# DRV8886_Power_Breakout.net
KiCad netlist of a schematic drawn in Altium Designer
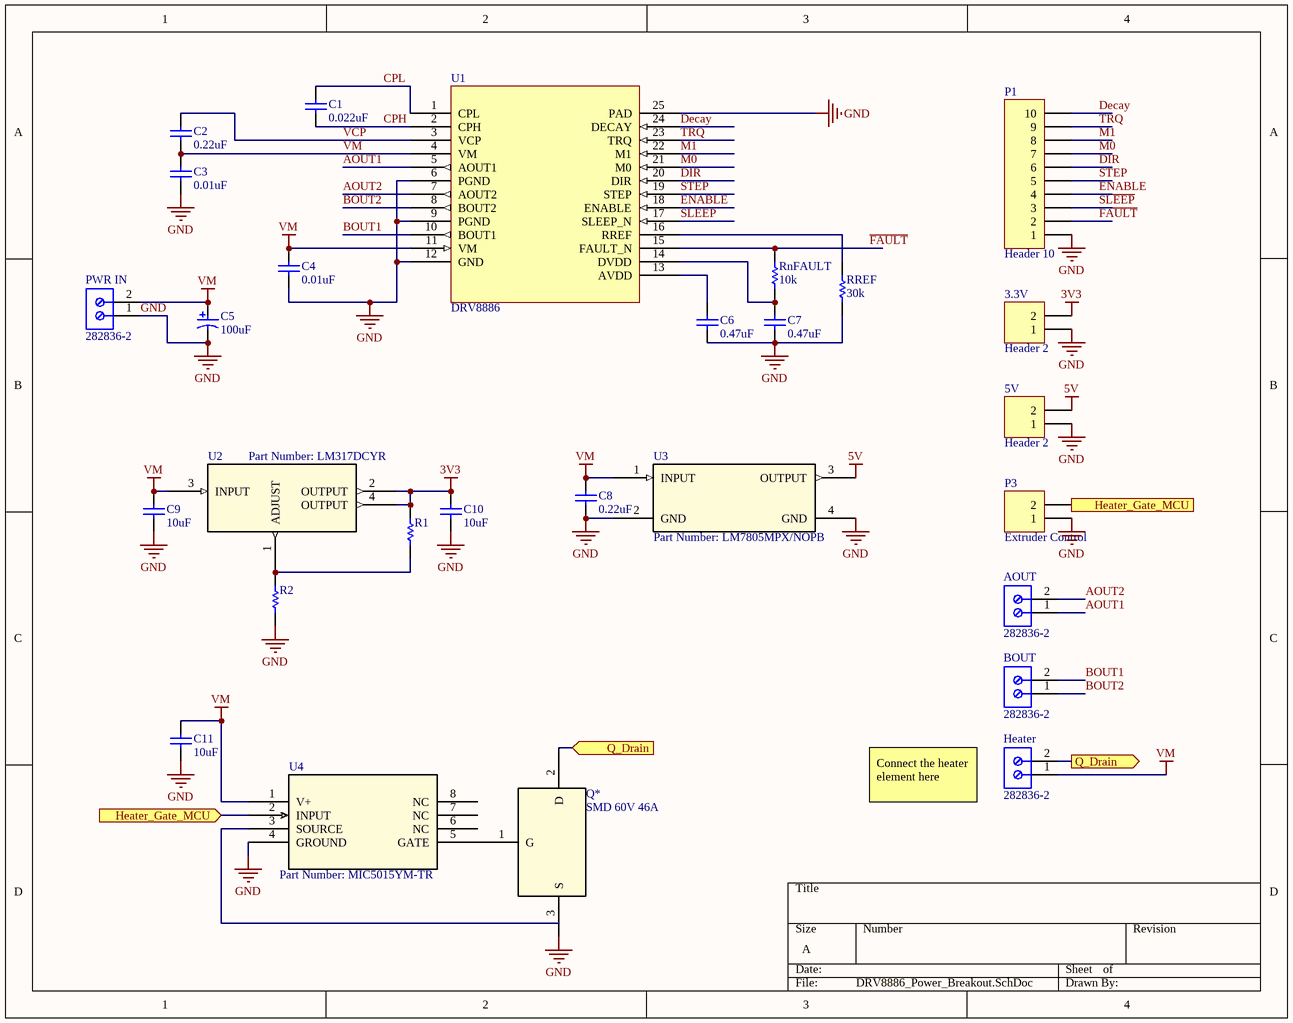
[diagram p0: DRV8886_Power_Breakout.SchDoc]

(export (version "E")
  (design (tool "Eeschema 10.0.6"))
  (components
    (comp (ref "3.3V")
      (value "Header 2")
      (footprint "HDR1X2")
      (description "Header, 2-Pin")
      (fields (field (name "PUBLISHER") "Altium Limited"))
      (libsource (lib "Miscellaneous Connectors") (part "Header 2"))
    )
    (comp (ref "5V")
      (value "Header 2")
      (footprint "HDR1X2")
      (description "Header, 2-Pin")
      (fields (field (name "PUBLISHER") "Altium Limited"))
      (libsource (lib "Miscellaneous Connectors") (part "Header 2"))
    )
    (comp (ref "AOUT")
      (value "282836-2")
      (footprint "TECO-282836-2_V")
      (description "Female Header, Pitch 5 mm, 1 x 2 Position, Height 10 mm, Tail Length 3.5 mm, Rohs, Bulk")
      (fields (field (name "VOLTAGE") "300V") (field (name "MANUFACTURER") "TE Connectivity"))
      (libsource (lib "IFFF_DRV8886_Power_Breakout") (part "CMP-1684-00017-1"))
    )
    (comp (ref "BOUT")
      (value "282836-2")
      (footprint "TECO-282836-2_V")
      (description "Female Header, Pitch 5 mm, 1 x 2 Position, Height 10 mm, Tail Length 3.5 mm, Rohs, Bulk")
      (fields (field (name "VOLTAGE") "300V") (field (name "MANUFACTURER") "TE Connectivity"))
      (libsource (lib "IFFF_DRV8886_Power_Breakout") (part "CMP-1684-00017-1"))
    )
    (comp (ref "C1")
      (value "0.022uF")
      (footprint "CAPC2013X94X50ML20T25")
      (fields
        (field (name "MANUFACTURER") "AVX Interconnect / Elco")
        (field (name "PART NUMBER") "08055C223JAT2A")
      )
      (libsource (lib "Altium Content Vault") (part "CAP"))
    )
    (comp (ref "C2")
      (value "0.22uF")
      (footprint "CAPC2013X145X50NL20T25")
      (description "0805")
      (fields (field (name "PART NUMBER") "C0805C224K5RAC7800") (field (name "MANUFACTURER") "Kemet"))
      (libsource (lib "Altium Content Vault") (part "CAP"))
    )
    (comp (ref "C3")
      (value "0.01uF")
      (footprint "CAPC2013X88X50ML20T25")
      (description "0805")
      (fields (field (name "MANUFACTURER") "Kemet") (field (name "PART NUMBER") "C0805C103J5RACTU"))
      (libsource (lib "Altium Content Vault") (part "CAP"))
    )
    (comp (ref "C4")
      (value "0.01uF")
      (footprint "CAPC2013X88X50ML20T25")
      (description "0805")
      (fields (field (name "MANUFACTURER") "Kemet") (field (name "PART NUMBER") "C0805C103J5RACTU"))
      (libsource (lib "Altium Content Vault") (part "CAP"))
    )
    (comp (ref "C5")
      (value "100uF")
      (footprint "PNSC-FK-V-F_V")
      (fields (field (name "MANUFACTURER") "Panasonic"))
      (libsource (lib "Altium Content Vault") (part "CAP-P-2"))
    )
    (comp (ref "C6")
      (value "0.47uF")
      (footprint "CAPC2013X110X50NL20T25")
      (description "0805")
      (fields (field (name "MANUFACTURER") "Kemet") (field (name "PART NUMBER") "C0805C474K5RACTU"))
      (libsource (lib "Altium Content Vault") (part "CAP"))
    )
    (comp (ref "C7")
      (value "0.47uF")
      (footprint "CAPC2013X110X50NL20T25")
      (description "0805")
      (fields (field (name "MANUFACTURER") "Kemet") (field (name "PART NUMBER") "C0805C474K5RACTU"))
      (libsource (lib "Altium Content Vault") (part "CAP"))
    )
    (comp (ref "C8")
      (value "0.22uF")
      (footprint "CAPC2013X145X50NL20T25")
      (description "0805")
      (fields (field (name "PART NUMBER") "C0805C224K5RAC7800") (field (name "MANUFACTURER") "Kemet"))
      (libsource (lib "Altium Content Vault") (part "CAP"))
    )
    (comp (ref "C9")
      (value "10uF")
      (footprint "CAPC2013X135X45ML10T25")
      (description "0805")
      (fields (field (name "PART NUMBER") "GRM21BR61E106KA73L") (field (name "MANUFACTURER") "Murata"))
      (libsource (lib "Altium Content Vault") (part "CAP"))
    )
    (comp (ref "C10")
      (value "10uF")
      (footprint "CAPC2013X135X45ML10T25")
      (description "0805")
      (fields (field (name "PART NUMBER") "GRM21BR61E106KA73L") (field (name "MANUFACTURER") "Murata"))
      (libsource (lib "Altium Content Vault") (part "CAP"))
    )
    (comp (ref "C11")
      (value "10uF")
      (footprint "CAPC2013X135X45ML10T25")
      (description "0805")
      (fields (field (name "PART NUMBER") "GRM21BR61E106KA73L") (field (name "MANUFACTURER") "Murata"))
      (libsource (lib "Altium Content Vault") (part "CAP"))
    )
    (comp (ref "Heater")
      (value "282836-2")
      (footprint "TECO-282836-2_V")
      (description "Female Header, Pitch 5 mm, 1 x 2 Position, Height 10 mm, Tail Length 3.5 mm, Rohs, Bulk")
      (fields (field (name "VOLTAGE") "300V") (field (name "MANUFACTURER") "TE Connectivity"))
      (libsource (lib "IFFF_DRV8886_Power_Breakout") (part "CMP-1684-00017-1"))
    )
    (comp (ref "P1")
      (value "Header 10")
      (footprint "HDR1X10")
      (description "Header, 10-Pin")
      (fields (field (name "PUBLISHER") "Altium Limited"))
      (libsource (lib "Miscellaneous Connectors") (part "Header 10"))
    )
    (comp (ref "P3")
      (value "Extruder Control")
      (footprint "HDR1X2")
      (description "Header, 2-Pin")
      (fields (field (name "PUBLISHER") "Altium Limited"))
      (libsource (lib "Miscellaneous Connectors") (part "Header 2"))
    )
    (comp (ref "PWR IN")
      (value "282836-2")
      (footprint "TECO-282836-2_V")
      (description "Female Header, Pitch 5 mm, 1 x 2 Position, Height 10 mm, Tail Length 3.5 mm, Rohs, Bulk")
      (fields (field (name "VOLTAGE") "300V") (field (name "MANUFACTURER") "TE Connectivity"))
      (libsource (lib "IFFF_DRV8886_Power_Breakout") (part "CMP-1684-00017-1"))
    )
    (comp (ref "Q*")
      (value "SMD 60V 46A")
      (footprint "SC_TO-252AA")
      (description "N-Channel 60V 46A (Tc) 71W (Tc) Surface Mount DPAK")
      (libsource (lib "IFFF_DRV8886_Power_Breakout") (part "NTD5865NLT4G"))
    )
    (comp (ref "R1")
      (value "~")
      (footprint "RESC2013X60X40LL20T25_A")
      (fields (field (name "TOLERANCE") "0.1%") (field (name "MANUFACTURER") "Panasonic"))
      (libsource (lib "Altium Content Vault") (part "RES-2"))
    )
    (comp (ref "R2")
      (value "~")
      (footprint "RESC2013X60X40LL20T25_A")
      (fields (field (name "TOLERANCE") "0.1%") (field (name "MANUFACTURER") "Panasonic"))
      (libsource (lib "Altium Content Vault") (part "RES-2"))
    )
    (comp (ref "RnFAULT")
      (value "10k")
      (footprint "RESC2013X60X40LL20T25_A")
      (fields (field (name "TOLERANCE") "0.1%") (field (name "MANUFACTURER") "Panasonic"))
      (libsource (lib "Altium Content Vault") (part "RES-2"))
    )
    (comp (ref "RREF")
      (value "30k")
      (footprint "RESC2013X60X40LL20T25_A")
      (fields (field (name "TOLERANCE") "0.1%") (field (name "MANUFACTURER") "Panasonic"))
      (libsource (lib "Altium Content Vault") (part "RES-2"))
    )
    (comp (ref "U1")
      (value "DRV8886")
      (footprint "PWP0024B_N")
      (libsource (lib "IFFF_DRV8886_Power_Breakout") (part "DRV8886"))
    )
    (comp (ref "U2")
      (value "Part Number: LM317DCYR")
      (footprint "DCY4")
      (description "No Description Available")
      (fields
        (field (name "MANUFACTURER_PART_NUMBER") "LM317DCYR")
        (field (name "COPYRIGHT") "Copyright (C) 2018 Accelerated Designs. All rights reserved")
      )
      (libsource (lib "IFFF_DRV8886_Power_Breakout") (part "LM317DCYR"))
    )
    (comp (ref "U3")
      (value "Part Number: LM7805MPX/NOPB")
      (footprint "DCY4")
      (description "No Description Available")
      (fields
        (field (name "MANUFACTURER_PART_NUMBER") "LM7805MPX/NOPB")
        (field (name "COPYRIGHT") "Copyright (C) 2018 Accelerated Designs. All rights reserved")
      )
      (libsource (lib "IFFF_DRV8886_Power_Breakout") (part "LM7805MPX/NOPB"))
    )
    (comp (ref "U4")
      (value "Part Number: MIC5015YM-TR")
      (footprint "SOIC-8_M")
      (description "No Description Available")
      (fields
        (field (name "MANUFACTURER_PART_NUMBER") "MIC5015YM-TR")
        (field (name "COPYRIGHT") "Copyright (C) 2018 Accelerated Designs. All rights reserved")
      )
      (libsource (lib "IFFF_DRV8886_Power_Breakout") (part "MIC5015YM-TR"))
    )
  )
  (nets
    (net (code "1") (name "/AOUT1") (class "Default")
      (node (ref "AOUT") (pin "1") (pinfunction "1_1") (pintype "passive"))
      (node (ref "U1") (pin "5") (pinfunction "AOUT1_5") (pintype "output"))
    )
    (net (code "2") (name "/AOUT2") (class "Default")
      (node (ref "AOUT") (pin "2") (pinfunction "2_2") (pintype "passive"))
      (node (ref "U1") (pin "7") (pinfunction "AOUT2_7") (pintype "output"))
    )
    (net (code "3") (name "/BOUT1") (class "Default")
      (node (ref "BOUT") (pin "2") (pinfunction "2_2") (pintype "passive"))
      (node (ref "U1") (pin "10") (pinfunction "BOUT1_10") (pintype "output"))
    )
    (net (code "4") (name "/BOUT2") (class "Default")
      (node (ref "BOUT") (pin "1") (pinfunction "1_1") (pintype "passive"))
      (node (ref "U1") (pin "8") (pinfunction "BOUT2_8") (pintype "output"))
    )
    (net (code "5") (name "/CPH") (class "Default")
      (node (ref "C1") (pin "1") (pinfunction "1_1") (pintype "passive"))
      (node (ref "U1") (pin "2") (pinfunction "CPH_2") (pintype "passive"))
    )
    (net (code "6") (name "/CPL") (class "Default")
      (node (ref "C1") (pin "2") (pinfunction "2_2") (pintype "passive"))
      (node (ref "U1") (pin "1") (pinfunction "CPL_1") (pintype "passive"))
    )
    (net (code "7") (name "/DIR") (class "Default")
      (node (ref "P1") (pin "6") (pinfunction "6_6") (pintype "passive"))
      (node (ref "U1") (pin "20") (pinfunction "DIR_20") (pintype "input"))
    )
    (net (code "8") (name "/Decay") (class "Default")
      (node (ref "P1") (pin "10") (pinfunction "10_10") (pintype "passive"))
      (node (ref "U1") (pin "24") (pinfunction "DECAY_24") (pintype "input"))
    )
    (net (code "9") (name "/ENABLE") (class "Default")
      (node (ref "P1") (pin "4") (pinfunction "4_4") (pintype "passive"))
      (node (ref "U1") (pin "18") (pinfunction "ENABLE_18") (pintype "input"))
    )
    (net (code "10") (name "/FAULT") (class "Default")
      (node (ref "P1") (pin "2") (pinfunction "2_2") (pintype "passive"))
      (node (ref "RnFAULT") (pin "2") (pinfunction "2_2") (pintype "passive"))
      (node (ref "U1") (pin "15") (pinfunction "FAULT_N_15") (pintype "passive"))
    )
    (net (code "11") (name "/Heater_Gate_MCU") (class "Default")
      (node (ref "P3") (pin "2") (pinfunction "2_2") (pintype "passive"))
      (node (ref "U4") (pin "2") (pinfunction "INPUT_2") (pintype "input"))
    )
    (net (code "12") (name "/M0") (class "Default")
      (node (ref "P1") (pin "7") (pinfunction "7_7") (pintype "passive"))
      (node (ref "U1") (pin "21") (pinfunction "M0_21") (pintype "input"))
    )
    (net (code "13") (name "/M1") (class "Default")
      (node (ref "P1") (pin "8") (pinfunction "8_8") (pintype "passive"))
      (node (ref "U1") (pin "22") (pinfunction "M1_22") (pintype "input"))
    )
    (net (code "14") (name "/Q_Drain") (class "Default")
      (node (ref "Heater") (pin "2") (pinfunction "2_2") (pintype "passive"))
      (node (ref "Q*") (pin "2") (pinfunction "D_2") (pintype "passive"))
    )
    (net (code "15") (name "/SLEEP") (class "Default")
      (node (ref "P1") (pin "3") (pinfunction "3_3") (pintype "passive"))
      (node (ref "U1") (pin "17") (pinfunction "SLEEP_N_17") (pintype "input"))
    )
    (net (code "16") (name "/STEP") (class "Default")
      (node (ref "P1") (pin "5") (pinfunction "5_5") (pintype "passive"))
      (node (ref "U1") (pin "19") (pinfunction "STEP_19") (pintype "input"))
    )
    (net (code "17") (name "/TRQ") (class "Default")
      (node (ref "P1") (pin "9") (pinfunction "9_9") (pintype "passive"))
      (node (ref "U1") (pin "23") (pinfunction "TRQ_23") (pintype "input"))
    )
    (net (code "18") (name "/VCP") (class "Default")
      (node (ref "C2") (pin "2") (pinfunction "2_2") (pintype "passive"))
      (node (ref "U1") (pin "3") (pinfunction "VCP_3") (pintype "passive"))
    )
    (net (code "19") (name "3V3") (class "Default")
      (node (ref "3.3V") (pin "2") (pinfunction "2_2") (pintype "passive"))
      (node (ref "C10") (pin "1") (pinfunction "1_1") (pintype "passive"))
      (node (ref "R1") (pin "2") (pinfunction "2_2") (pintype "passive"))
      (node (ref "U2") (pin "2") (pinfunction "OUTPUT_2") (pintype "output"))
      (node (ref "U2") (pin "4") (pinfunction "OUTPUT_4") (pintype "output"))
    )
    (net (code "20") (name "5V") (class "Default")
      (node (ref "5V") (pin "2") (pinfunction "2_2") (pintype "passive"))
      (node (ref "U3") (pin "3") (pinfunction "OUTPUT_3") (pintype "output"))
    )
    (net (code "21") (name "GND") (class "Default")
      (node (ref "3.3V") (pin "1") (pinfunction "1_1") (pintype "passive"))
      (node (ref "5V") (pin "1") (pinfunction "1_1") (pintype "passive"))
      (node (ref "C10") (pin "2") (pinfunction "2_2") (pintype "passive"))
      (node (ref "C11") (pin "2") (pinfunction "2_2") (pintype "passive"))
      (node (ref "C3") (pin "1") (pinfunction "1_1") (pintype "passive"))
      (node (ref "C4") (pin "1") (pinfunction "1_1") (pintype "passive"))
      (node (ref "C5") (pin "2") (pinfunction "2_2") (pintype "passive"))
      (node (ref "C6") (pin "1") (pinfunction "1_1") (pintype "passive"))
      (node (ref "C7") (pin "1") (pinfunction "1_1") (pintype "passive"))
      (node (ref "C8") (pin "1") (pinfunction "1_1") (pintype "passive"))
      (node (ref "C9") (pin "2") (pinfunction "2_2") (pintype "passive"))
      (node (ref "P1") (pin "1") (pinfunction "1_1") (pintype "passive"))
      (node (ref "P3") (pin "1") (pinfunction "1_1") (pintype "passive"))
      (node (ref "PWR IN") (pin "1") (pinfunction "1_1") (pintype "passive"))
      (node (ref "Q*") (pin "3") (pinfunction "S_3") (pintype "passive"))
      (node (ref "R2") (pin "1") (pinfunction "1_1") (pintype "passive"))
      (node (ref "RREF") (pin "1") (pinfunction "1_1") (pintype "passive"))
      (node (ref "U1") (pin "12") (pinfunction "GND_12") (pintype "passive"))
      (node (ref "U1") (pin "25") (pinfunction "PAD_25") (pintype "passive"))
      (node (ref "U1") (pin "6") (pinfunction "PGND_6") (pintype "passive"))
      (node (ref "U1") (pin "9") (pinfunction "PGND_9") (pintype "passive"))
      (node (ref "U3") (pin "2") (pinfunction "GND_2") (pintype "power_in"))
      (node (ref "U3") (pin "4") (pinfunction "GND_4") (pintype "power_in"))
      (node (ref "U4") (pin "4") (pinfunction "GROUND_4") (pintype "power_in"))
    )
    (net (code "22") (name "Net-(Q*-G)") (class "Default")
      (node (ref "Q*") (pin "1") (pinfunction "G_1") (pintype "passive"))
      (node (ref "U4") (pin "5") (pinfunction "GATE_5") (pintype "passive"))
    )
    (net (code "23") (name "Net-(U1-AVDD)") (class "Default")
      (node (ref "C6") (pin "2") (pinfunction "2_2") (pintype "passive"))
      (node (ref "U1") (pin "13") (pinfunction "AVDD_13") (pintype "passive"))
    )
    (net (code "24") (name "Net-(U1-DVDD)") (class "Default")
      (node (ref "C7") (pin "2") (pinfunction "2_2") (pintype "passive"))
      (node (ref "RnFAULT") (pin "1") (pinfunction "1_1") (pintype "passive"))
      (node (ref "U1") (pin "14") (pinfunction "DVDD_14") (pintype "passive"))
    )
    (net (code "25") (name "Net-(U1-RREF)") (class "Default")
      (node (ref "RREF") (pin "2") (pinfunction "2_2") (pintype "passive"))
      (node (ref "U1") (pin "16") (pinfunction "RREF_16") (pintype "passive"))
    )
    (net (code "26") (name "Net-(U2-ADJUST)") (class "Default")
      (node (ref "R1") (pin "1") (pinfunction "1_1") (pintype "passive"))
      (node (ref "R2") (pin "2") (pinfunction "2_2") (pintype "passive"))
      (node (ref "U2") (pin "1") (pinfunction "ADJUST_1") (pintype "output"))
    )
    (net (code "27") (name "VM") (class "Default")
      (node (ref "C11") (pin "1") (pinfunction "1_1") (pintype "passive"))
      (node (ref "C2") (pin "1") (pinfunction "1_1") (pintype "passive"))
      (node (ref "C3") (pin "2") (pinfunction "2_2") (pintype "passive"))
      (node (ref "C4") (pin "2") (pinfunction "2_2") (pintype "passive"))
      (node (ref "C5") (pin "1") (pinfunction "1_1") (pintype "passive"))
      (node (ref "C8") (pin "2") (pinfunction "2_2") (pintype "passive"))
      (node (ref "C9") (pin "1") (pinfunction "1_1") (pintype "passive"))
      (node (ref "Heater") (pin "1") (pinfunction "1_1") (pintype "passive"))
      (node (ref "PWR IN") (pin "2") (pinfunction "2_2") (pintype "passive"))
      (node (ref "U1") (pin "11") (pinfunction "VM_11") (pintype "input"))
      (node (ref "U1") (pin "4") (pinfunction "VM_4") (pintype "passive"))
      (node (ref "U2") (pin "3") (pinfunction "INPUT_3") (pintype "input"))
      (node (ref "U3") (pin "1") (pinfunction "INPUT_1") (pintype "input"))
      (node (ref "U4") (pin "1") (pinfunction "V+_1") (pintype "power_in"))
    )
    (net (code "28") (name "unconnected-(U4-NC-Pad6)") (class "Default")
      (node (ref "U4") (pin "6") (pinfunction "NC_6") (pintype "passive"))
    )
    (net (code "29") (name "unconnected-(U4-NC-Pad7)") (class "Default")
      (node (ref "U4") (pin "7") (pinfunction "NC_7") (pintype "passive"))
    )
    (net (code "30") (name "unconnected-(U4-NC-Pad8)") (class "Default")
      (node (ref "U4") (pin "8") (pinfunction "NC_8") (pintype "passive"))
    )
    (net (code "31") (name "unconnected-(U4-SOURCE-Pad3)") (class "Default")
      (node (ref "U4") (pin "3") (pinfunction "SOURCE_3") (pintype "passive"))
    )
  )
)
